# pms7003-adapter.net
KiCad netlist of a schematic drawn in EAGLE
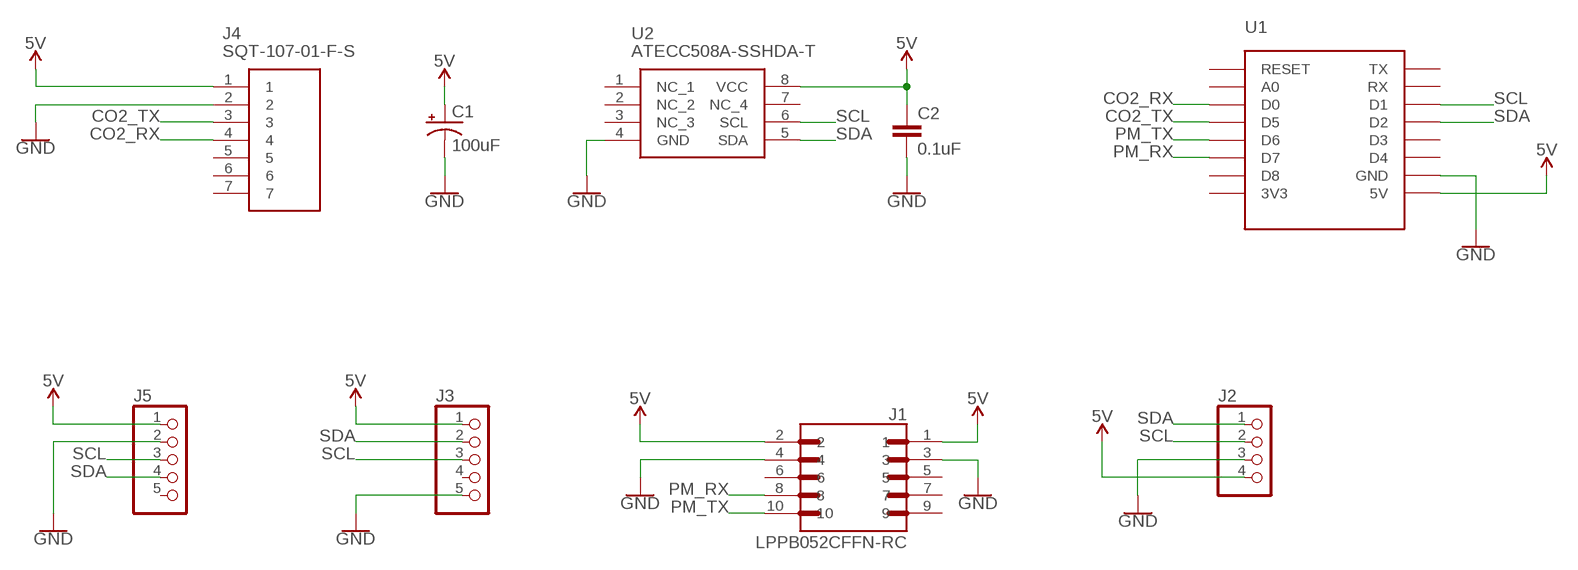
[diagram p0: schematic, sheet 1]

(export (version "E")
  (design (tool "Eeschema 10.0.6"))
  (components
    (comp (ref "C1")
      (value "100uF")
      (footprint "eagle-import:CPOL-RADIAL-2.5MM-6.5MM")
      (libsource (lib "eagle-import") (part "100UF-POLAR-RADIAL-2.5MM-25V-20%"))
    )
    (comp (ref "C2")
      (value "0.1uF")
      (footprint "eagle-import:0603")
      (libsource (lib "eagle-import") (part "0.1UF-0603-25V-(+80/-20%)"))
    )
    (comp (ref "J1")
      (value "LPPB052CFFN-RC")
      (footprint "eagle-import:SULLINS_LPPB052CFFN-RC")
      (fields (field (name "DIGI-KEY_PART_NUMBER") "S9009E-05-ND") (field (name "MF") "Sullins"))
      (libsource (lib "eagle-import") (part "LPPB052CFFN-RC"))
    )
    (comp (ref "J2")
      (value "PINHD-1X4")
      (footprint "eagle-import:1X04")
      (libsource (lib "eagle-import") (part "PINHD-1X4"))
    )
    (comp (ref "J3")
      (value "PINHD-1X5")
      (footprint "eagle-import:1X05")
      (libsource (lib "eagle-import") (part "PINHD-1X5"))
    )
    (comp (ref "J4")
      (value "SQT-107-01-F-S")
      (footprint "eagle-import:SQT-107-01-XX-S")
      (fields (field (name "MOUSER_PART_NUMBER") "200-SQT10701FS"))
      (libsource (lib "eagle-import") (part "SQT-107-01-F-S"))
    )
    (comp (ref "J5")
      (value "PINHD-1X5")
      (footprint "eagle-import:1X05")
      (libsource (lib "eagle-import") (part "PINHD-1X5"))
    )
    (comp (ref "U1")
      (value "WEMOS-D1-MINI")
      (footprint "eagle-import:WEMOS-D1-MINI")
      (libsource (lib "eagle-import") (part "WEMOS-D1-MINI"))
    )
    (comp (ref "U2")
      (value "ATECC508A-SSHDA-T")
      (footprint "eagle-import:SOIC127P600X175-8N")
      (fields (field (name "MOUSER_PART_NUMBER") "556-ATECC508A-SSHDAT"))
      (libsource (lib "eagle-import") (part "ATECC508A-SSHDA-T"))
    )
  )
  (nets
    (net (code "1") (name "/CO2_RX") (class "Default")
      (node (ref "J4") (pin "4") (pinfunction "4_4") (pintype "bidirectional"))
      (node (ref "U1") (pin "D0") (pinfunction "D0_D0") (pintype "bidirectional"))
    )
    (net (code "2") (name "/CO2_TX") (class "Default")
      (node (ref "J4") (pin "3") (pinfunction "3_3") (pintype "bidirectional"))
      (node (ref "U1") (pin "D5") (pinfunction "D5_D5") (pintype "bidirectional"))
    )
    (net (code "3") (name "/PM_RX") (class "Default")
      (node (ref "J1") (pin "8") (pinfunction "8_8") (pintype "passive"))
      (node (ref "U1") (pin "D7") (pinfunction "D7_D7") (pintype "bidirectional"))
    )
    (net (code "4") (name "/PM_TX") (class "Default")
      (node (ref "J1") (pin "10") (pinfunction "10_10") (pintype "passive"))
      (node (ref "U1") (pin "D6") (pinfunction "D6_D6") (pintype "bidirectional"))
    )
    (net (code "5") (name "/SCL") (class "Default")
      (node (ref "J2") (pin "2") (pinfunction "2_2") (pintype "passive"))
      (node (ref "J3") (pin "3") (pinfunction "3_3") (pintype "passive"))
      (node (ref "J5") (pin "3") (pinfunction "3_3") (pintype "passive"))
      (node (ref "U1") (pin "D1") (pinfunction "D1_D1") (pintype "bidirectional"))
      (node (ref "U2") (pin "6") (pinfunction "SCL_6") (pintype "bidirectional"))
    )
    (net (code "6") (name "/SDA") (class "Default")
      (node (ref "J2") (pin "1") (pinfunction "1_1") (pintype "passive"))
      (node (ref "J3") (pin "2") (pinfunction "2_2") (pintype "passive"))
      (node (ref "J5") (pin "4") (pinfunction "4_4") (pintype "passive"))
      (node (ref "U1") (pin "D2") (pinfunction "D2_D2") (pintype "bidirectional"))
      (node (ref "U2") (pin "5") (pinfunction "SDA_5") (pintype "bidirectional"))
    )
    (net (code "7") (name "5V") (class "Default")
      (node (ref "C1") (pin "1") (pinfunction "+_1") (pintype "passive"))
      (node (ref "C2") (pin "1") (pinfunction "1_1") (pintype "passive"))
      (node (ref "J1") (pin "1") (pinfunction "1_1") (pintype "passive"))
      (node (ref "J1") (pin "2") (pinfunction "2_2") (pintype "passive"))
      (node (ref "J2") (pin "4") (pinfunction "4_4") (pintype "passive"))
      (node (ref "J3") (pin "1") (pinfunction "1_1") (pintype "passive"))
      (node (ref "J4") (pin "1") (pinfunction "1_1") (pintype "bidirectional"))
      (node (ref "J5") (pin "1") (pinfunction "1_1") (pintype "passive"))
      (node (ref "U1") (pin "5V") (pinfunction "5V_5V") (pintype "bidirectional"))
      (node (ref "U2") (pin "8") (pinfunction "VCC_8") (pintype "bidirectional"))
    )
    (net (code "8") (name "GND") (class "Default")
      (node (ref "C1") (pin "2") (pinfunction "-_2") (pintype "passive"))
      (node (ref "C2") (pin "2") (pinfunction "2_2") (pintype "passive"))
      (node (ref "J1") (pin "3") (pinfunction "3_3") (pintype "passive"))
      (node (ref "J1") (pin "4") (pinfunction "4_4") (pintype "passive"))
      (node (ref "J2") (pin "3") (pinfunction "3_3") (pintype "passive"))
      (node (ref "J3") (pin "5") (pinfunction "5_5") (pintype "passive"))
      (node (ref "J4") (pin "2") (pinfunction "2_2") (pintype "bidirectional"))
      (node (ref "J5") (pin "2") (pinfunction "2_2") (pintype "passive"))
      (node (ref "U1") (pin "GND") (pinfunction "GND_GND") (pintype "bidirectional"))
      (node (ref "U2") (pin "4") (pinfunction "GND_4") (pintype "bidirectional"))
    )
    (net (code "9") (name "unconnected-(J1-Pad5)") (class "Default")
      (node (ref "J1") (pin "5") (pinfunction "5_5") (pintype "passive"))
    )
    (net (code "10") (name "unconnected-(J1-Pad6)") (class "Default")
      (node (ref "J1") (pin "6") (pinfunction "6_6") (pintype "passive"))
    )
    (net (code "11") (name "unconnected-(J1-Pad7)") (class "Default")
      (node (ref "J1") (pin "7") (pinfunction "7_7") (pintype "passive"))
    )
    (net (code "12") (name "unconnected-(J1-Pad9)") (class "Default")
      (node (ref "J1") (pin "9") (pinfunction "9_9") (pintype "passive"))
    )
    (net (code "13") (name "unconnected-(J3-Pad4)") (class "Default")
      (node (ref "J3") (pin "4") (pinfunction "4_4") (pintype "passive"))
    )
    (net (code "14") (name "unconnected-(J4-Pad5)") (class "Default")
      (node (ref "J4") (pin "5") (pinfunction "5_5") (pintype "bidirectional"))
    )
    (net (code "15") (name "unconnected-(J4-Pad6)") (class "Default")
      (node (ref "J4") (pin "6") (pinfunction "6_6") (pintype "bidirectional"))
    )
    (net (code "16") (name "unconnected-(J4-Pad7)") (class "Default")
      (node (ref "J4") (pin "7") (pinfunction "7_7") (pintype "bidirectional"))
    )
    (net (code "17") (name "unconnected-(J5-Pad5)") (class "Default")
      (node (ref "J5") (pin "5") (pinfunction "5_5") (pintype "passive"))
    )
    (net (code "18") (name "unconnected-(U1-Pad3V3)") (class "Default")
      (node (ref "U1") (pin "3V3") (pinfunction "3V3_3V3") (pintype "bidirectional"))
    )
    (net (code "19") (name "unconnected-(U1-PadA0)") (class "Default")
      (node (ref "U1") (pin "A0") (pinfunction "A0_A0") (pintype "bidirectional"))
    )
    (net (code "20") (name "unconnected-(U1-PadD3)") (class "Default")
      (node (ref "U1") (pin "D3") (pinfunction "D3_D3") (pintype "bidirectional"))
    )
    (net (code "21") (name "unconnected-(U1-PadD4)") (class "Default")
      (node (ref "U1") (pin "D4") (pinfunction "D4_D4") (pintype "bidirectional"))
    )
    (net (code "22") (name "unconnected-(U1-PadD8)") (class "Default")
      (node (ref "U1") (pin "D8") (pinfunction "D8_D8") (pintype "bidirectional"))
    )
    (net (code "23") (name "unconnected-(U1-PadRX)") (class "Default")
      (node (ref "U1") (pin "RX") (pinfunction "RX_RX") (pintype "bidirectional"))
    )
    (net (code "24") (name "unconnected-(U1-PadTX)") (class "Default")
      (node (ref "U1") (pin "TX") (pinfunction "TX_TX") (pintype "bidirectional"))
    )
    (net (code "25") (name "unconnected-(U1-RESET-PadRST)") (class "Default")
      (node (ref "U1") (pin "RST") (pinfunction "RESET_RST") (pintype "bidirectional"))
    )
    (net (code "26") (name "unconnected-(U2-NC_1-Pad1)") (class "Default")
      (node (ref "U2") (pin "1") (pinfunction "NC_1_1") (pintype "bidirectional"))
    )
    (net (code "27") (name "unconnected-(U2-NC_2-Pad2)") (class "Default")
      (node (ref "U2") (pin "2") (pinfunction "NC_2_2") (pintype "bidirectional"))
    )
    (net (code "28") (name "unconnected-(U2-NC_3-Pad3)") (class "Default")
      (node (ref "U2") (pin "3") (pinfunction "NC_3_3") (pintype "bidirectional"))
    )
    (net (code "29") (name "unconnected-(U2-NC_4-Pad7)") (class "Default")
      (node (ref "U2") (pin "7") (pinfunction "NC_4_7") (pintype "bidirectional"))
    )
  )
)
